# PowerWB.net
KiCad netlist of a schematic drawn in Altium Designer
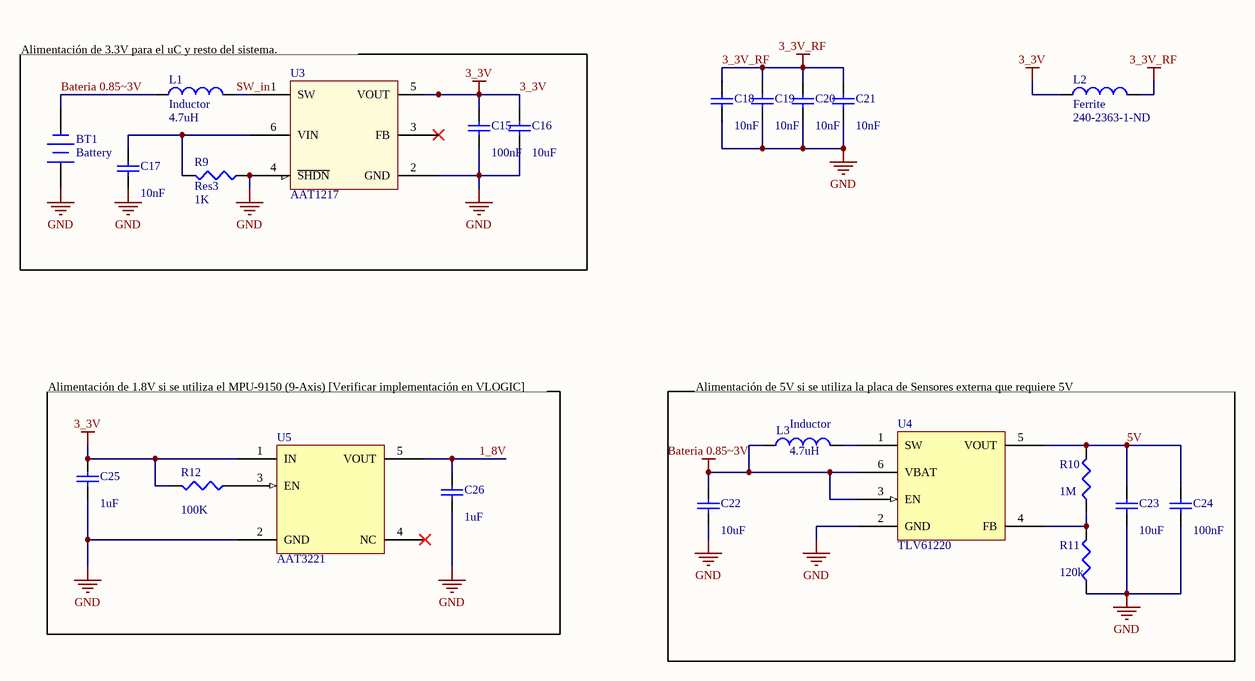
[diagram p0: PowerWB.SchDoc]

(export (version "E")
  (design (tool "Eeschema 10.0.6"))
  (components
    (comp (ref "BT1")
      (value "Battery")
      (footprint "BAT-2")
      (description "Multicell Battery")
      (fields (field (name "PUBLISHER") "Altium Limited"))
      (libsource (lib "Miscellaneous Devices") (part "Battery"))
    )
    (comp (ref "C15")
      (value "100nF")
      (footprint "1608[0603]")
      (description "Capacitor (Semiconductor SIM Model)")
      (fields (field (name "Comment") "Cap Semi") (field (name "PUBLISHER") "Altium Limited"))
      (libsource (lib "Miscellaneous Devices") (part "Cap Semi"))
    )
    (comp (ref "C16")
      (value "10uF")
      (footprint "1608[0603]")
      (description "Capacitor (Semiconductor SIM Model)")
      (fields (field (name "Comment") "Cap Semi") (field (name "PUBLISHER") "Altium Limited"))
      (libsource (lib "Miscellaneous Devices") (part "Cap Semi"))
    )
    (comp (ref "C17")
      (value "10nF")
      (footprint "1608[0603]")
      (description "Capacitor (Semiconductor SIM Model)")
      (fields (field (name "Comment") "Cap Semi") (field (name "PUBLISHER") "Altium Limited"))
      (libsource (lib "Miscellaneous Devices") (part "Cap Semi"))
    )
    (comp (ref "C18")
      (value "10nF")
      (footprint "1608[0603]")
      (description "Capacitor (Semiconductor SIM Model)")
      (fields (field (name "Comment") "Cap Semi") (field (name "PUBLISHER") "Altium Limited"))
      (libsource (lib "Miscellaneous Devices") (part "Cap Semi"))
    )
    (comp (ref "C19")
      (value "10nF")
      (footprint "1608[0603]")
      (description "Capacitor (Semiconductor SIM Model)")
      (fields (field (name "Comment") "Cap Semi") (field (name "PUBLISHER") "Altium Limited"))
      (libsource (lib "Miscellaneous Devices") (part "Cap Semi"))
    )
    (comp (ref "C20")
      (value "10nF")
      (footprint "1608[0603]")
      (description "Capacitor (Semiconductor SIM Model)")
      (fields (field (name "Comment") "Cap Semi") (field (name "PUBLISHER") "Altium Limited"))
      (libsource (lib "Miscellaneous Devices") (part "Cap Semi"))
    )
    (comp (ref "C21")
      (value "10nF")
      (footprint "1608[0603]")
      (description "Capacitor (Semiconductor SIM Model)")
      (fields (field (name "Comment") "Cap Semi") (field (name "PUBLISHER") "Altium Limited"))
      (libsource (lib "Miscellaneous Devices") (part "Cap Semi"))
    )
    (comp (ref "C22")
      (value "10uF")
      (footprint "C0805")
      (description "Capacitor (Semiconductor SIM Model)")
      (fields (field (name "Comment") "Cap Semi") (field (name "PUBLISHER") "Altium Limited"))
      (libsource (lib "Miscellaneous Devices") (part "Cap Semi"))
    )
    (comp (ref "C23")
      (value "10uF")
      (footprint "C0805")
      (description "Capacitor (Semiconductor SIM Model)")
      (fields (field (name "Comment") "Cap Semi") (field (name "PUBLISHER") "Altium Limited"))
      (libsource (lib "Miscellaneous Devices") (part "Cap Semi"))
    )
    (comp (ref "C24")
      (value "100nF")
      (footprint "C0805")
      (description "Capacitor (Semiconductor SIM Model)")
      (fields (field (name "Comment") "Cap Semi") (field (name "PUBLISHER") "Altium Limited"))
      (libsource (lib "Miscellaneous Devices") (part "Cap Semi"))
    )
    (comp (ref "C25")
      (value "1uF")
      (footprint "1608[0603]")
      (description "Capacitor (Semiconductor SIM Model)")
      (fields (field (name "Comment") "Cap Semi") (field (name "PUBLISHER") "Altium Limited"))
      (libsource (lib "Miscellaneous Devices") (part "Cap Semi"))
    )
    (comp (ref "C26")
      (value "1uF")
      (footprint "1608[0603]")
      (description "Capacitor (Semiconductor SIM Model)")
      (fields (field (name "Comment") "Cap Semi") (field (name "PUBLISHER") "Altium Limited"))
      (libsource (lib "Miscellaneous Devices") (part "Cap Semi"))
    )
    (comp (ref "L1")
      (value "Inductor")
      (footprint "0402-A")
      (fields (field (name "ALTIUM_VALUE") "4.7uH") (field (name "PUBLISHER") "Altium Limited"))
      (libsource (lib "Miscellaneous Devices") (part "Inductor"))
    )
    (comp (ref "L2")
      (value "Ferrite")
      (footprint "0402-A")
      (description "Inductor")
      (fields (field (name "ALTIUM_VALUE") "240-2363-1-ND") (field (name "PUBLISHER") "Altium Limited"))
      (libsource (lib "Miscellaneous Devices") (part "Inductor"))
    )
    (comp (ref "L3")
      (value "Inductor")
      (footprint "0402-A")
      (fields (field (name "ALTIUM_VALUE") "4.7uH") (field (name "PUBLISHER") "Altium Limited"))
      (libsource (lib "Miscellaneous Devices") (part "Inductor"))
    )
    (comp (ref "R9")
      (value "Res3")
      (footprint "6-0805_M")
      (description "Resistor")
      (fields (field (name "ALTIUM_VALUE") "1K") (field (name "PUBLISHER") "Altium Limited"))
      (libsource (lib "Miscellaneous Devices") (part "Res3"))
    )
    (comp (ref "R10")
      (value "1M")
      (footprint "6-0805_M")
      (description "Resistor")
      (fields (field (name "Comment") "Res3") (field (name "PUBLISHER") "Altium Limited"))
      (libsource (lib "Miscellaneous Devices") (part "Res3"))
    )
    (comp (ref "R11")
      (value "120k")
      (footprint "6-0805_M")
      (description "Resistor")
      (fields (field (name "Comment") "Res3") (field (name "PUBLISHER") "Altium Limited"))
      (libsource (lib "Miscellaneous Devices") (part "Res3"))
    )
    (comp (ref "R12")
      (value "100K")
      (footprint "6-0805_M")
      (description "Resistor")
      (fields (field (name "Comment") "Res3") (field (name "PUBLISHER") "Altium Limited"))
      (libsource (lib "Miscellaneous Devices") (part "Res3"))
    )
    (comp (ref "U3") (value "AAT1217") (footprint "SOT26A-6N") (libsource (lib "sch_comp") (part "AAT1217")))
    (comp (ref "U4")
      (value "TLV61220")
      (footprint "SOT26A-6N")
      (description "LOW INPUT VOLTAGE STEP-UP CONVERTER IN THIN SOT-23 PACKAGE")
      (libsource (lib "sch_comp") (part "TLV61220"))
    )
    (comp (ref "U5")
      (value "AAT3221")
      (description "IC REG LDO 1.8V 0.15A SOT23-5")
      (libsource (lib "sch_comp") (part "AAT3221"))
    )
  )
  (nets
    (net (code "1") (name "/1_8V") (class "Default")
      (node (ref "C26") (pin "2") (pinfunction "2_2") (pintype "passive"))
      (node (ref "U5") (pin "5") (pinfunction "VOUT_5") (pintype "power_in"))
    )
    (net (code "2") (name "/5V") (class "Default")
      (node (ref "C23") (pin "2") (pinfunction "2_2") (pintype "passive"))
      (node (ref "C24") (pin "2") (pinfunction "2_2") (pintype "passive"))
      (node (ref "R10") (pin "2") (pinfunction "2_2") (pintype "passive"))
      (node (ref "U4") (pin "5") (pinfunction "VOUT_5") (pintype "power_in"))
    )
    (net (code "3") (name "/SW_in") (class "Default")
      (node (ref "L1") (pin "2") (pinfunction "2_2") (pintype "passive"))
      (node (ref "U3") (pin "1") (pinfunction "SW_1") (pintype "power_in"))
    )
    (net (code "4") (name "3_3V") (class "Default")
      (node (ref "C15") (pin "2") (pinfunction "2_2") (pintype "passive"))
      (node (ref "C16") (pin "2") (pinfunction "2_2") (pintype "passive"))
      (node (ref "C25") (pin "2") (pinfunction "2_2") (pintype "passive"))
      (node (ref "L2") (pin "1") (pinfunction "1_1") (pintype "passive"))
      (node (ref "R12") (pin "2") (pinfunction "2_2") (pintype "passive"))
      (node (ref "U3") (pin "5") (pinfunction "VOUT_5") (pintype "power_in"))
      (node (ref "U5") (pin "1") (pinfunction "IN_1") (pintype "power_in"))
    )
    (net (code "5") (name "3_3V_RF") (class "Default")
      (node (ref "C18") (pin "2") (pinfunction "2_2") (pintype "passive"))
      (node (ref "C19") (pin "2") (pinfunction "2_2") (pintype "passive"))
      (node (ref "C20") (pin "2") (pinfunction "2_2") (pintype "passive"))
      (node (ref "C21") (pin "2") (pinfunction "2_2") (pintype "passive"))
      (node (ref "L2") (pin "2") (pinfunction "2_2") (pintype "passive"))
    )
    (net (code "6") (name "Bateria 0.85~3V") (class "Default")
      (node (ref "BT1") (pin "2") (pinfunction "-_2") (pintype "passive"))
      (node (ref "C22") (pin "2") (pinfunction "2_2") (pintype "passive"))
      (node (ref "L1") (pin "1") (pinfunction "1_1") (pintype "passive"))
      (node (ref "L3") (pin "1") (pinfunction "1_1") (pintype "passive"))
      (node (ref "U4") (pin "3") (pinfunction "EN_3") (pintype "input"))
      (node (ref "U4") (pin "6") (pinfunction "VBAT_6") (pintype "power_in"))
    )
    (net (code "7") (name "GND") (class "Default")
      (node (ref "BT1") (pin "1") (pinfunction "+_1") (pintype "passive"))
      (node (ref "C15") (pin "1") (pinfunction "1_1") (pintype "passive"))
      (node (ref "C16") (pin "1") (pinfunction "1_1") (pintype "passive"))
      (node (ref "C17") (pin "1") (pinfunction "1_1") (pintype "passive"))
      (node (ref "C18") (pin "1") (pinfunction "1_1") (pintype "passive"))
      (node (ref "C19") (pin "1") (pinfunction "1_1") (pintype "passive"))
      (node (ref "C20") (pin "1") (pinfunction "1_1") (pintype "passive"))
      (node (ref "C21") (pin "1") (pinfunction "1_1") (pintype "passive"))
      (node (ref "C22") (pin "1") (pinfunction "1_1") (pintype "passive"))
      (node (ref "C23") (pin "1") (pinfunction "1_1") (pintype "passive"))
      (node (ref "C24") (pin "1") (pinfunction "1_1") (pintype "passive"))
      (node (ref "C25") (pin "1") (pinfunction "1_1") (pintype "passive"))
      (node (ref "C26") (pin "1") (pinfunction "1_1") (pintype "passive"))
      (node (ref "R11") (pin "1") (pinfunction "1_1") (pintype "passive"))
      (node (ref "R9") (pin "1") (pinfunction "1_1") (pintype "passive"))
      (node (ref "U3") (pin "2") (pinfunction "GND_2") (pintype "power_in"))
      (node (ref "U3") (pin "4") (pinfunction "~{SHDN}_4") (pintype "passive"))
      (node (ref "U4") (pin "2") (pinfunction "GND_2") (pintype "power_in"))
      (node (ref "U5") (pin "2") (pinfunction "GND_2") (pintype "power_in"))
    )
    (net (code "8") (name "Net-(U3-VIN)") (class "Default")
      (node (ref "C17") (pin "2") (pinfunction "2_2") (pintype "passive"))
      (node (ref "R9") (pin "2") (pinfunction "2_2") (pintype "passive"))
      (node (ref "U3") (pin "6") (pinfunction "VIN_6") (pintype "power_in"))
    )
    (net (code "9") (name "Net-(U4-FB)") (class "Default")
      (node (ref "R10") (pin "1") (pinfunction "1_1") (pintype "passive"))
      (node (ref "R11") (pin "2") (pinfunction "2_2") (pintype "passive"))
      (node (ref "U4") (pin "4") (pinfunction "FB_4") (pintype "passive"))
    )
    (net (code "10") (name "Net-(U4-SW)") (class "Default")
      (node (ref "L3") (pin "2") (pinfunction "2_2") (pintype "passive"))
      (node (ref "U4") (pin "1") (pinfunction "SW_1") (pintype "passive"))
    )
    (net (code "11") (name "Net-(U5-EN)") (class "Default")
      (node (ref "R12") (pin "1") (pinfunction "1_1") (pintype "passive"))
      (node (ref "U5") (pin "3") (pinfunction "EN_3") (pintype "input"))
    )
    (net (code "12") (name "unconnected-(U3-FB-Pad3)") (class "Default")
      (node (ref "U3") (pin "3") (pinfunction "FB_3") (pintype "passive+no_connect"))
    )
    (net (code "13") (name "unconnected-(U5-NC-Pad4)") (class "Default")
      (node (ref "U5") (pin "4") (pinfunction "NC_4") (pintype "passive+no_connect"))
    )
  )
)
